# robotShield_CPU.net
KiCad netlist of a schematic drawn in Altium Designer
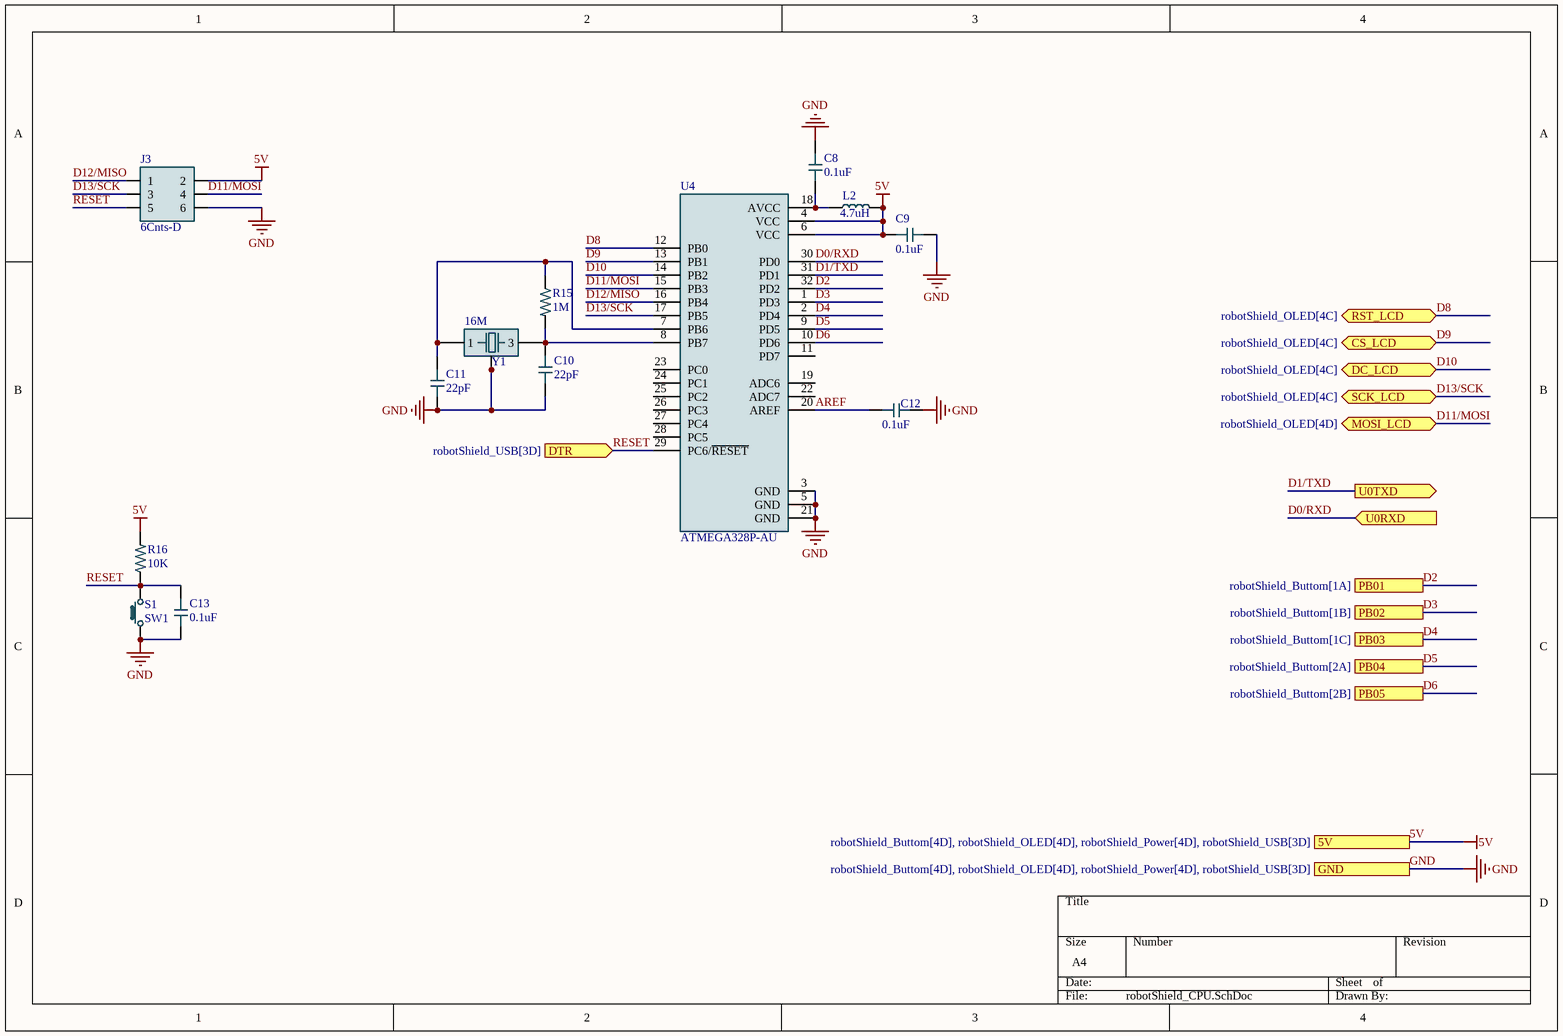
[diagram p0: robotShield_CPU.SchDoc]

(export (version "E")
  (design (tool "Eeschema 10.0.6"))
  (components
    (comp (ref "C8")
      (value "0.1uF")
      (footprint "CAP0603")
      (description "CAP SMD")
      (fields (field (name "MF") "AVX") (field (name "MP") "LD031A101GAB2A"))
      (libsource (lib "Hossein72T") (part "Capacitor"))
    )
    (comp (ref "C9")
      (value "0.1uF")
      (footprint "CAP0603")
      (description "CAP SMD")
      (fields (field (name "MF") "AVX") (field (name "MP") "LD031A101GAB2A"))
      (libsource (lib "Hossein72T") (part "Capacitor"))
    )
    (comp (ref "C10")
      (value "22pF")
      (footprint "CAP0603")
      (description "CAP SMD")
      (fields (field (name "MF") "AVX") (field (name "MP") "LD031A101GAB2A"))
      (libsource (lib "Hossein72T") (part "Capacitor"))
    )
    (comp (ref "C11")
      (value "22pF")
      (footprint "CAP0603")
      (description "CAP SMD")
      (fields (field (name "MF") "AVX") (field (name "MP") "LD031A101GAB2A"))
      (libsource (lib "Hossein72T") (part "Capacitor"))
    )
    (comp (ref "C12")
      (value "0.1uF")
      (footprint "CAP0603")
      (description "CAP SMD")
      (fields (field (name "MF") "AVX") (field (name "MP") "LD031A101GAB2A"))
      (libsource (lib "Hossein72T") (part "Capacitor"))
    )
    (comp (ref "C13")
      (value "0.1uF")
      (footprint "CAP0603")
      (description "CAP SMD")
      (fields (field (name "MF") "AVX") (field (name "MP") "LD031A101GAB2A"))
      (libsource (lib "Hossein72T") (part "Capacitor"))
    )
    (comp (ref "J3")
      (value "6Cnts-D")
      (footprint "6Cnts-D-SMD")
      (fields (field (name "MP") "MTSW-103-22-S-D-430"))
      (libsource (lib "Hossein72T") (part "6Cnts-D"))
    )
    (comp (ref "L2")
      (value "4.7uH")
      (footprint "Inductor0603")
      (description "Inductor with Inductance 6.8uH Tol.+/-20%")
      (fields (field (name "MP") "LQM18DN6R8M70B"))
      (libsource (lib "Hossein72T") (part "Inductor"))
    )
    (comp (ref "R15")
      (value "1M")
      (footprint "RES0603")
      (description "RES 0.27 OHM 1% 1/10W")
      (fields (field (name "MP") "3-1879460-5") (field (name "MF") "TE Connectivity"))
      (libsource (lib "Hossein72T") (part "Resistor"))
    )
    (comp (ref "R16")
      (value "10K")
      (footprint "RES0603")
      (description "RES 0.27 OHM 1% 1/10W")
      (fields (field (name "MP") "3-1879460-5") (field (name "MF") "TE Connectivity"))
      (libsource (lib "Hossein72T") (part "Resistor"))
    )
    (comp (ref "S1")
      (value "SW1")
      (footprint "Pushbutton_Tactile")
      (description "Switch,Pushbutton,Tactile,SPST")
      (libsource (lib "Hossein72T") (part "Pushbutton"))
    )
    (comp (ref "U4")
      (value "ATMEGA328P-AU")
      (footprint "ATMEGA328P-AU")
      (description "AVR ATmega Microcontroller IC 8-Bit 20MHz 32KB (16K x 16) FLASH 32-TQFP (7x7)")
      (fields (field (name "MF") "Microchip"))
      (libsource (lib "Hossein72T") (part "ATMEGA328P-AU"))
    )
    (comp (ref "Y1")
      (value "16M")
      (footprint "crystal-2520")
      (description "40MHz 10pF ±10ppm SMD-4P Crystals")
      (fields (field (name "MF") "EPSON") (field (name "MP") "TSX-3225 16.0000MF18X-AC3"))
      (libsource (lib "Hossein72T") (part "crystal-4P"))
    )
  )
  (nets
    (net (code "1") (name "/AREF") (class "Default")
      (node (ref "C12") (pin "1") (pinfunction "1_1") (pintype "passive"))
      (node (ref "U4") (pin "20") (pinfunction "AREF_20") (pintype "passive"))
    )
    (net (code "2") (name "/D0{slash}RXD") (class "Default")
      (node (ref "U4") (pin "30") (pinfunction "PD0_30") (pintype "passive"))
    )
    (net (code "3") (name "/D1{slash}TXD") (class "Default")
      (node (ref "U4") (pin "31") (pinfunction "PD1_31") (pintype "passive"))
    )
    (net (code "4") (name "/D2") (class "Default")
      (node (ref "U4") (pin "32") (pinfunction "PD2_32") (pintype "passive"))
    )
    (net (code "5") (name "/D3") (class "Default")
      (node (ref "U4") (pin "1") (pinfunction "PD3_1") (pintype "passive"))
    )
    (net (code "6") (name "/D4") (class "Default")
      (node (ref "U4") (pin "2") (pinfunction "PD4_2") (pintype "passive"))
    )
    (net (code "7") (name "/D5") (class "Default")
      (node (ref "U4") (pin "9") (pinfunction "PD5_9") (pintype "passive"))
    )
    (net (code "8") (name "/D6") (class "Default")
      (node (ref "U4") (pin "10") (pinfunction "PD6_10") (pintype "passive"))
    )
    (net (code "9") (name "/D8") (class "Default")
      (node (ref "U4") (pin "12") (pinfunction "PB0_12") (pintype "passive"))
    )
    (net (code "10") (name "/D9") (class "Default")
      (node (ref "U4") (pin "13") (pinfunction "PB1_13") (pintype "passive"))
    )
    (net (code "11") (name "/D10") (class "Default")
      (node (ref "U4") (pin "14") (pinfunction "PB2_14") (pintype "passive"))
    )
    (net (code "12") (name "/D11{slash}MOSI") (class "Default")
      (node (ref "J3") (pin "4") (pinfunction "4_4") (pintype "passive"))
      (node (ref "U4") (pin "15") (pinfunction "PB3_15") (pintype "passive"))
    )
    (net (code "13") (name "/D12{slash}MISO") (class "Default")
      (node (ref "J3") (pin "1") (pinfunction "1_1") (pintype "passive"))
      (node (ref "U4") (pin "16") (pinfunction "PB4_16") (pintype "passive"))
    )
    (net (code "14") (name "/D13{slash}SCK") (class "Default")
      (node (ref "J3") (pin "3") (pinfunction "3_3") (pintype "passive"))
      (node (ref "U4") (pin "17") (pinfunction "PB5_17") (pintype "passive"))
    )
    (net (code "15") (name "/RESET") (class "Default")
      (node (ref "C13") (pin "1") (pinfunction "1_1") (pintype "passive"))
      (node (ref "J3") (pin "5") (pinfunction "5_5") (pintype "passive"))
      (node (ref "R16") (pin "1") (pinfunction "1_1") (pintype "passive"))
      (node (ref "S1") (pin "2") (pinfunction "2_2") (pintype "passive"))
      (node (ref "U4") (pin "29") (pinfunction "PC6/~{RESET}_29") (pintype "passive"))
    )
    (net (code "16") (name "5V") (class "Default")
      (node (ref "C9") (pin "1") (pinfunction "1_1") (pintype "passive"))
      (node (ref "J3") (pin "2") (pinfunction "2_2") (pintype "passive"))
      (node (ref "L2") (pin "2") (pinfunction "2_2") (pintype "passive"))
      (node (ref "R16") (pin "2") (pinfunction "2_2") (pintype "passive"))
      (node (ref "U4") (pin "4") (pinfunction "VCC_4") (pintype "power_in"))
      (node (ref "U4") (pin "6") (pinfunction "VCC_6") (pintype "power_in"))
    )
    (net (code "17") (name "GND") (class "Default")
      (node (ref "C10") (pin "2") (pinfunction "2_2") (pintype "passive"))
      (node (ref "C11") (pin "2") (pinfunction "2_2") (pintype "passive"))
      (node (ref "C12") (pin "2") (pinfunction "2_2") (pintype "passive"))
      (node (ref "C13") (pin "2") (pinfunction "2_2") (pintype "passive"))
      (node (ref "C8") (pin "1") (pinfunction "1_1") (pintype "passive"))
      (node (ref "C9") (pin "2") (pinfunction "2_2") (pintype "passive"))
      (node (ref "J3") (pin "6") (pinfunction "6_6") (pintype "passive"))
      (node (ref "S1") (pin "1") (pinfunction "1_1") (pintype "passive"))
      (node (ref "U4") (pin "21") (pinfunction "GND_21") (pintype "power_in"))
      (node (ref "U4") (pin "3") (pinfunction "GND_3") (pintype "power_in"))
      (node (ref "U4") (pin "5") (pinfunction "GND_5") (pintype "power_in"))
      (node (ref "Y1") (pin "2") (pinfunction "GND_2") (pintype "power_in"))
      (node (ref "Y1") (pin "4") (pinfunction "GND_4") (pintype "power_in"))
    )
    (net (code "18") (name "Net-(U4-AVCC)") (class "Default")
      (node (ref "C8") (pin "2") (pinfunction "2_2") (pintype "passive"))
      (node (ref "L2") (pin "1") (pinfunction "1_1") (pintype "passive"))
      (node (ref "U4") (pin "18") (pinfunction "AVCC_18") (pintype "power_in"))
    )
    (net (code "19") (name "Net-(U4-PB6)") (class "Default")
      (node (ref "C11") (pin "1") (pinfunction "1_1") (pintype "passive"))
      (node (ref "R15") (pin "1") (pinfunction "1_1") (pintype "passive"))
      (node (ref "U4") (pin "7") (pinfunction "PB6_7") (pintype "passive"))
      (node (ref "Y1") (pin "1") (pinfunction "1_1") (pintype "passive"))
    )
    (net (code "20") (name "Net-(U4-PB7)") (class "Default")
      (node (ref "C10") (pin "1") (pinfunction "1_1") (pintype "passive"))
      (node (ref "R15") (pin "2") (pinfunction "2_2") (pintype "passive"))
      (node (ref "U4") (pin "8") (pinfunction "PB7_8") (pintype "passive"))
      (node (ref "Y1") (pin "3") (pinfunction "3_3") (pintype "passive"))
    )
    (net (code "21") (name "unconnected-(U4-ADC6-Pad19)") (class "Default")
      (node (ref "U4") (pin "19") (pinfunction "ADC6_19") (pintype "passive"))
    )
    (net (code "22") (name "unconnected-(U4-ADC7-Pad22)") (class "Default")
      (node (ref "U4") (pin "22") (pinfunction "ADC7_22") (pintype "passive"))
    )
    (net (code "23") (name "unconnected-(U4-PC0-Pad23)") (class "Default")
      (node (ref "U4") (pin "23") (pinfunction "PC0_23") (pintype "passive"))
    )
    (net (code "24") (name "unconnected-(U4-PC1-Pad24)") (class "Default")
      (node (ref "U4") (pin "24") (pinfunction "PC1_24") (pintype "passive"))
    )
    (net (code "25") (name "unconnected-(U4-PC2-Pad25)") (class "Default")
      (node (ref "U4") (pin "25") (pinfunction "PC2_25") (pintype "passive"))
    )
    (net (code "26") (name "unconnected-(U4-PC3-Pad26)") (class "Default")
      (node (ref "U4") (pin "26") (pinfunction "PC3_26") (pintype "passive"))
    )
    (net (code "27") (name "unconnected-(U4-PC4-Pad27)") (class "Default")
      (node (ref "U4") (pin "27") (pinfunction "PC4_27") (pintype "passive"))
    )
    (net (code "28") (name "unconnected-(U4-PC5-Pad28)") (class "Default")
      (node (ref "U4") (pin "28") (pinfunction "PC5_28") (pintype "passive"))
    )
    (net (code "29") (name "unconnected-(U4-PD7-Pad11)") (class "Default")
      (node (ref "U4") (pin "11") (pinfunction "PD7_11") (pintype "passive"))
    )
  )
)
